# sensorluz_01.net
KiCad netlist of a schematic drawn in EAGLE
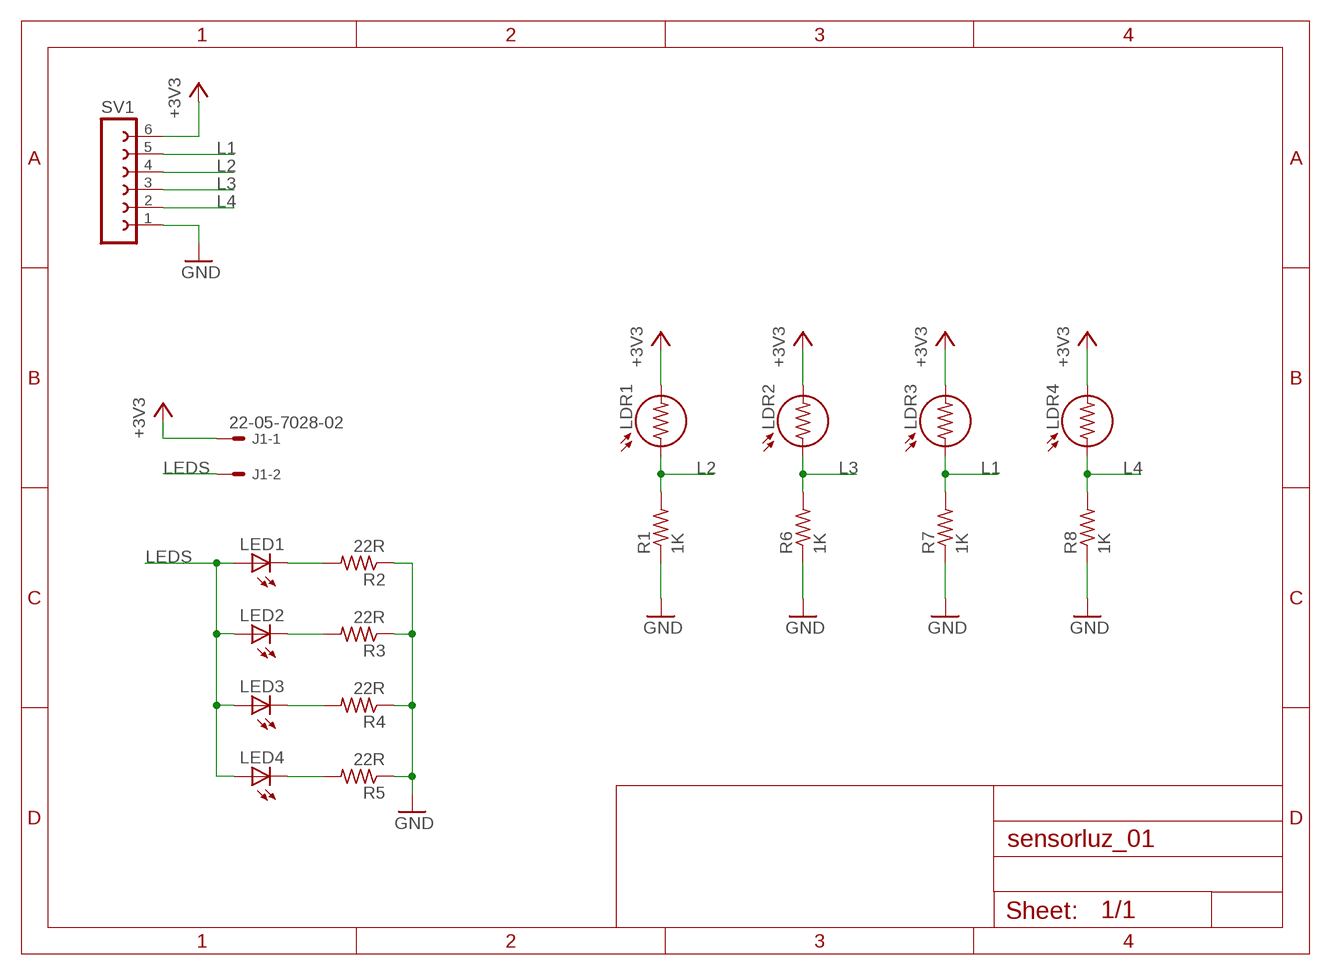
[diagram p0: schematic, sheet 1]

(export (version "E")
  (design (tool "Eeschema 10.0.6"))
  (components
    (comp (ref "J1")
      (value "22-05-7028-02")
      (footprint "eagle-import:7395-02")
      (libsource (lib "eagle-import") (part "22-?-0205-7028"))
    )
    (comp (ref "LDR1")
      (value "LDR5MM")
      (footprint "eagle-import:LDR338-54C")
      (libsource (lib "eagle-import") (part "LDR5MM"))
    )
    (comp (ref "LDR2")
      (value "LDR5MM")
      (footprint "eagle-import:LDR338-54C")
      (libsource (lib "eagle-import") (part "LDR5MM"))
    )
    (comp (ref "LDR3")
      (value "LDR5MM")
      (footprint "eagle-import:LDR338-54C")
      (libsource (lib "eagle-import") (part "LDR5MM"))
    )
    (comp (ref "LDR4")
      (value "LDR5MM")
      (footprint "eagle-import:LDR338-54C")
      (libsource (lib "eagle-import") (part "LDR5MM"))
    )
    (comp (ref "LED1")
      (value "LED5MM")
      (footprint "eagle-import:LED5MM")
      (libsource (lib "eagle-import") (part "LED5MM"))
    )
    (comp (ref "LED2")
      (value "LED5MM")
      (footprint "eagle-import:LED5MM")
      (libsource (lib "eagle-import") (part "LED5MM"))
    )
    (comp (ref "LED3")
      (value "LED5MM")
      (footprint "eagle-import:LED5MM")
      (libsource (lib "eagle-import") (part "LED5MM"))
    )
    (comp (ref "LED4")
      (value "LED5MM")
      (footprint "eagle-import:LED5MM")
      (libsource (lib "eagle-import") (part "LED5MM"))
    )
    (comp (ref "R1")
      (value "1K")
      (footprint "eagle-import:0204_5")
      (libsource (lib "eagle-import") (part "R-US_0204/5"))
    )
    (comp (ref "R2")
      (value "22R")
      (footprint "eagle-import:0204_5")
      (libsource (lib "eagle-import") (part "R-US_0204/5"))
    )
    (comp (ref "R3")
      (value "22R")
      (footprint "eagle-import:0204_5")
      (libsource (lib "eagle-import") (part "R-US_0204/5"))
    )
    (comp (ref "R4")
      (value "22R")
      (footprint "eagle-import:0204_5")
      (libsource (lib "eagle-import") (part "R-US_0204/5"))
    )
    (comp (ref "R5")
      (value "22R")
      (footprint "eagle-import:0204_5")
      (libsource (lib "eagle-import") (part "R-US_0204/5"))
    )
    (comp (ref "R6")
      (value "1K")
      (footprint "eagle-import:0204_5")
      (libsource (lib "eagle-import") (part "R-US_0204/5"))
    )
    (comp (ref "R7")
      (value "1K")
      (footprint "eagle-import:0204_5")
      (libsource (lib "eagle-import") (part "R-US_0204/5"))
    )
    (comp (ref "R8")
      (value "1K")
      (footprint "eagle-import:0204_5")
      (libsource (lib "eagle-import") (part "R-US_0204/5"))
    )
    (comp (ref "SV1")
      (value "FE06W")
      (footprint "eagle-import:FE06W")
      (libsource (lib "eagle-import") (part "FE06W"))
    )
  )
  (nets
    (net (code "1") (name "+3V3") (class "Default")
      (node (ref "J1") (pin "1") (pinfunction "S_1") (pintype "passive"))
      (node (ref "LDR1") (pin "2") (pinfunction "2_2") (pintype "passive"))
      (node (ref "LDR2") (pin "2") (pinfunction "2_2") (pintype "passive"))
      (node (ref "LDR3") (pin "2") (pinfunction "2_2") (pintype "passive"))
      (node (ref "LDR4") (pin "2") (pinfunction "2_2") (pintype "passive"))
      (node (ref "SV1") (pin "6") (pinfunction "6_6") (pintype "passive"))
    )
    (net (code "2") (name "/L1") (class "Default")
      (node (ref "LDR3") (pin "1") (pinfunction "1_1") (pintype "passive"))
      (node (ref "R7") (pin "2") (pinfunction "2_2") (pintype "passive"))
      (node (ref "SV1") (pin "5") (pinfunction "5_5") (pintype "passive"))
    )
    (net (code "3") (name "/L2") (class "Default")
      (node (ref "LDR1") (pin "1") (pinfunction "1_1") (pintype "passive"))
      (node (ref "R1") (pin "2") (pinfunction "2_2") (pintype "passive"))
      (node (ref "SV1") (pin "4") (pinfunction "4_4") (pintype "passive"))
    )
    (net (code "4") (name "/L3") (class "Default")
      (node (ref "LDR2") (pin "1") (pinfunction "1_1") (pintype "passive"))
      (node (ref "R6") (pin "2") (pinfunction "2_2") (pintype "passive"))
      (node (ref "SV1") (pin "3") (pinfunction "3_3") (pintype "passive"))
    )
    (net (code "5") (name "/L4") (class "Default")
      (node (ref "LDR4") (pin "1") (pinfunction "1_1") (pintype "passive"))
      (node (ref "R8") (pin "2") (pinfunction "2_2") (pintype "passive"))
      (node (ref "SV1") (pin "2") (pinfunction "2_2") (pintype "passive"))
    )
    (net (code "6") (name "/LEDS") (class "Default")
      (node (ref "J1") (pin "2") (pinfunction "S_2") (pintype "passive"))
      (node (ref "LED1") (pin "A") (pinfunction "A_A") (pintype "passive"))
      (node (ref "LED2") (pin "A") (pinfunction "A_A") (pintype "passive"))
      (node (ref "LED3") (pin "A") (pinfunction "A_A") (pintype "passive"))
      (node (ref "LED4") (pin "A") (pinfunction "A_A") (pintype "passive"))
    )
    (net (code "7") (name "GND") (class "Default")
      (node (ref "R1") (pin "1") (pinfunction "1_1") (pintype "passive"))
      (node (ref "R2") (pin "1") (pinfunction "1_1") (pintype "passive"))
      (node (ref "R3") (pin "1") (pinfunction "1_1") (pintype "passive"))
      (node (ref "R4") (pin "1") (pinfunction "1_1") (pintype "passive"))
      (node (ref "R5") (pin "1") (pinfunction "1_1") (pintype "passive"))
      (node (ref "R6") (pin "1") (pinfunction "1_1") (pintype "passive"))
      (node (ref "R7") (pin "1") (pinfunction "1_1") (pintype "passive"))
      (node (ref "R8") (pin "1") (pinfunction "1_1") (pintype "passive"))
      (node (ref "SV1") (pin "1") (pinfunction "1_1") (pintype "passive"))
    )
    (net (code "8") (name "Net-(LED1-C)") (class "Default")
      (node (ref "LED1") (pin "K") (pinfunction "C_K") (pintype "passive"))
      (node (ref "R2") (pin "2") (pinfunction "2_2") (pintype "passive"))
    )
    (net (code "9") (name "Net-(LED2-C)") (class "Default")
      (node (ref "LED2") (pin "K") (pinfunction "C_K") (pintype "passive"))
      (node (ref "R3") (pin "2") (pinfunction "2_2") (pintype "passive"))
    )
    (net (code "10") (name "Net-(LED3-C)") (class "Default")
      (node (ref "LED3") (pin "K") (pinfunction "C_K") (pintype "passive"))
      (node (ref "R4") (pin "2") (pinfunction "2_2") (pintype "passive"))
    )
    (net (code "11") (name "Net-(LED4-C)") (class "Default")
      (node (ref "LED4") (pin "K") (pinfunction "C_K") (pintype "passive"))
      (node (ref "R5") (pin "2") (pinfunction "2_2") (pintype "passive"))
    )
  )
)
